# schematic.net
KiCad netlist of a schematic drawn in EAGLE
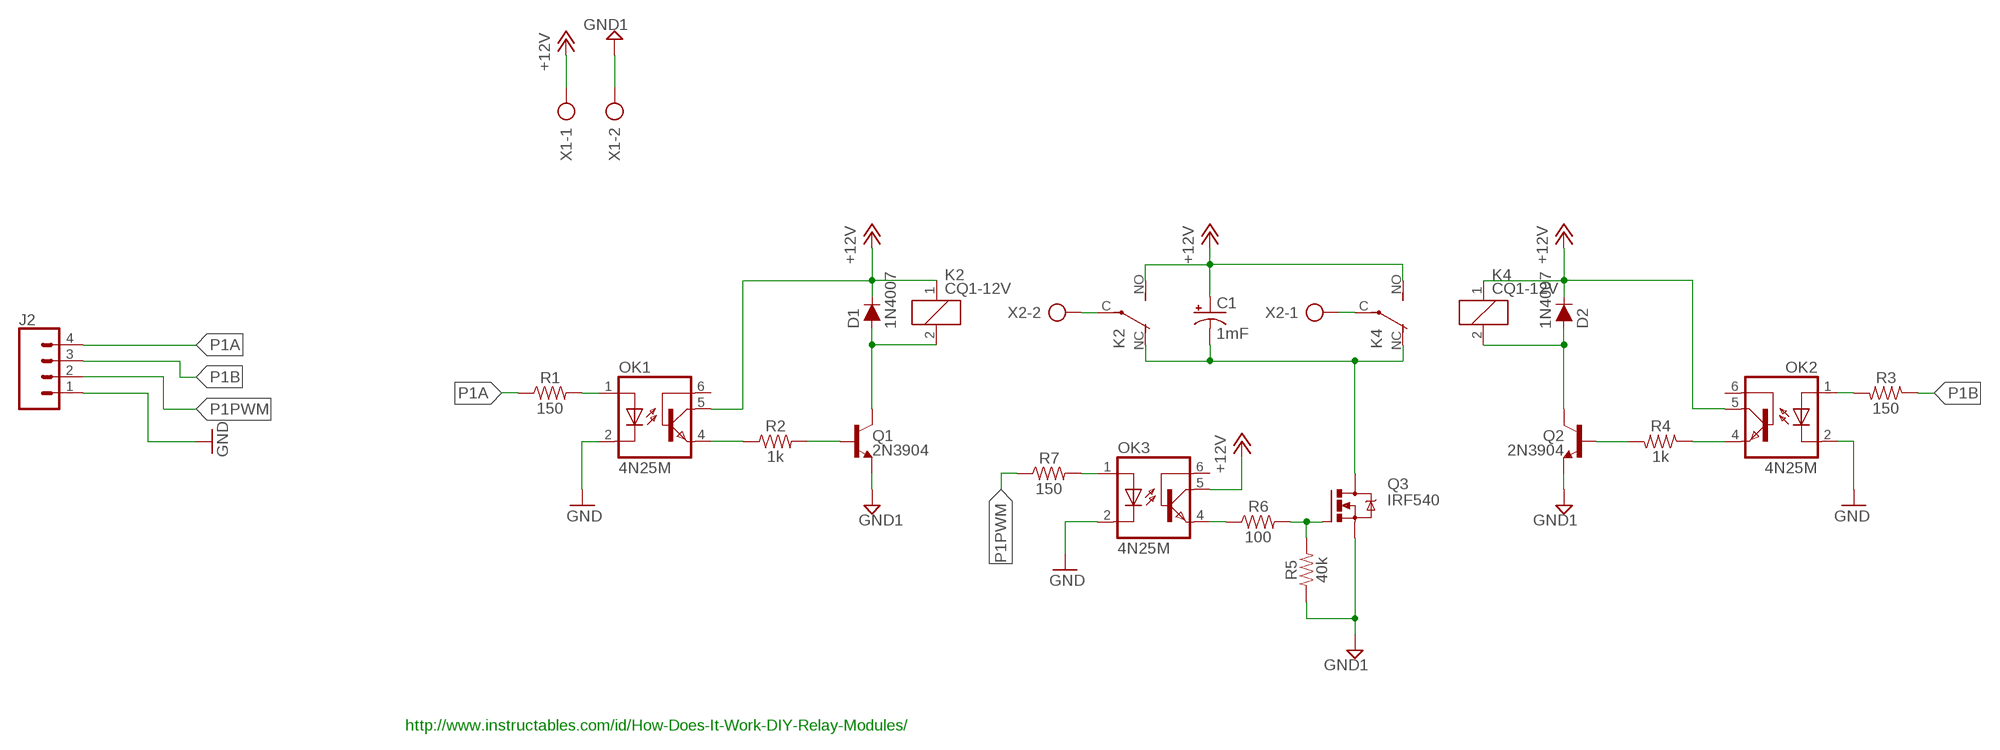
[diagram p0: schematic, sheet 1]

(export (version "E")
  (design (tool "Eeschema 10.0.6"))
  (components
    (comp (ref "C1")
      (value "1mF")
      (footprint "eagle-import:CPOL-RADIAL-5MM-10MM")
      (libsource (lib "eagle-import") (part "1000UF-RADIAL-5MM-25V-20%"))
    )
    (comp (ref "D1")
      (value "1N4007")
      (footprint "eagle-import:DIODE-1N4001")
      (libsource (lib "eagle-import") (part "DIODE-PTH"))
    )
    (comp (ref "D2")
      (value "1N4007")
      (footprint "eagle-import:DIODE-1N4001")
      (libsource (lib "eagle-import") (part "DIODE-PTH"))
    )
    (comp (ref "J2")
      (value "CONN_04LOCK_LONGPADS")
      (footprint "eagle-import:1X04_LOCK_LONGPADS")
      (libsource (lib "eagle-import") (part "CONN_04LOCK_LONGPADS"))
    )
    (comp (ref "K2")
      (value "CQ1-12V")
      (footprint "eagle-import:CQ1")
      (libsource (lib "eagle-import") (part "CQ1-12V"))
    )
    (comp (ref "K4")
      (value "CQ1-12V")
      (footprint "eagle-import:CQ1")
      (libsource (lib "eagle-import") (part "CQ1-12V"))
    )
    (comp (ref "OK1")
      (value "4N25M")
      (footprint "eagle-import:DIL06")
      (fields (field (name "MPN") "4N25-M"))
      (libsource (lib "eagle-import") (part "4N?M25"))
    )
    (comp (ref "OK2")
      (value "4N25M")
      (footprint "eagle-import:DIL06")
      (fields (field (name "MPN") "4N25-M"))
      (libsource (lib "eagle-import") (part "4N?M25"))
    )
    (comp (ref "OK3")
      (value "4N25M")
      (footprint "eagle-import:DIL06")
      (fields (field (name "MPN") "4N25-M"))
      (libsource (lib "eagle-import") (part "4N?M25"))
    )
    (comp (ref "Q1")
      (value "2N3904")
      (footprint "eagle-import:TO-92")
      (libsource (lib "eagle-import") (part "TRANS_NPN-2N3904"))
    )
    (comp (ref "Q2")
      (value "2N3904")
      (footprint "eagle-import:TO-92")
      (libsource (lib "eagle-import") (part "TRANS_NPN-2N3904"))
    )
    (comp (ref "Q3")
      (value "IRF540")
      (footprint "eagle-import:TO220BV")
      (libsource (lib "eagle-import") (part "IRF540"))
    )
    (comp (ref "R1")
      (value "150")
      (footprint "eagle-import:AXIAL-0.3")
      (libsource (lib "eagle-import") (part "10KOHM-HORIZ-1/4W-1%"))
    )
    (comp (ref "R2")
      (value "1k")
      (footprint "eagle-import:AXIAL-0.3")
      (libsource (lib "eagle-import") (part "10KOHM-HORIZ-1/4W-1%"))
    )
    (comp (ref "R3")
      (value "150")
      (footprint "eagle-import:AXIAL-0.3")
      (libsource (lib "eagle-import") (part "10KOHM-HORIZ-1/4W-1%"))
    )
    (comp (ref "R4")
      (value "1k")
      (footprint "eagle-import:AXIAL-0.3")
      (libsource (lib "eagle-import") (part "10KOHM-HORIZ-1/4W-1%"))
    )
    (comp (ref "R5")
      (value "40k")
      (footprint "eagle-import:AXIAL-0.3")
      (libsource (lib "eagle-import") (part "10KOHM-HORIZ-1/4W-1%"))
    )
    (comp (ref "R6")
      (value "100")
      (footprint "eagle-import:AXIAL-0.3")
      (libsource (lib "eagle-import") (part "10KOHM-HORIZ-1/4W-1%"))
    )
    (comp (ref "R7")
      (value "150")
      (footprint "eagle-import:AXIAL-0.3")
      (libsource (lib "eagle-import") (part "10KOHM-HORIZ-1/4W-1%"))
    )
    (comp (ref "X1")
      (value "AK300/2")
      (footprint "eagle-import:AK300_2")
      (libsource (lib "eagle-import") (part "AK300/2"))
    )
    (comp (ref "X2")
      (value "AK300/2")
      (footprint "eagle-import:AK300_2")
      (libsource (lib "eagle-import") (part "AK300/2"))
    )
  )
  (nets
    (net (code "1") (name "+12V") (class "Default")
      (node (ref "C1") (pin "+") (pinfunction "+_+") (pintype "passive"))
      (node (ref "D1") (pin "C") (pinfunction "C_C") (pintype "passive"))
      (node (ref "D2") (pin "C") (pinfunction "C_C") (pintype "passive"))
      (node (ref "K2") (pin "1") (pinfunction "1_1") (pintype "passive"))
      (node (ref "K2") (pin "NO") (pinfunction "S_NO") (pintype "passive"))
      (node (ref "K4") (pin "1") (pinfunction "1_1") (pintype "passive"))
      (node (ref "K4") (pin "NO") (pinfunction "S_NO") (pintype "passive"))
      (node (ref "OK1") (pin "5") (pinfunction "COL_5") (pintype "passive"))
      (node (ref "OK2") (pin "5") (pinfunction "COL_5") (pintype "passive"))
      (node (ref "OK3") (pin "5") (pinfunction "COL_5") (pintype "passive"))
      (node (ref "X1") (pin "1") (pinfunction "KL_1") (pintype "passive"))
    )
    (net (code "2") (name "GND") (class "Default")
      (node (ref "J2") (pin "1") (pinfunction "1_1") (pintype "passive"))
      (node (ref "OK1") (pin "2") (pinfunction "C_2") (pintype "passive"))
      (node (ref "OK2") (pin "2") (pinfunction "C_2") (pintype "passive"))
      (node (ref "OK3") (pin "2") (pinfunction "C_2") (pintype "passive"))
    )
    (net (code "3") (name "GND1") (class "Default")
      (node (ref "Q1") (pin "1") (pinfunction "E_1") (pintype "passive"))
      (node (ref "Q2") (pin "1") (pinfunction "E_1") (pintype "passive"))
      (node (ref "Q3") (pin "S") (pinfunction "S_S") (pintype "passive"))
      (node (ref "R5") (pin "P$1") (pinfunction "1_P$1") (pintype "passive"))
      (node (ref "X1") (pin "2") (pinfunction "KL_2") (pintype "passive"))
    )
    (net (code "4") (name "Net-(K2B-O)") (class "Default")
      (node (ref "C1") (pin "-") (pinfunction "-_-") (pintype "passive"))
      (node (ref "K2") (pin "NC") (pinfunction "O_NC") (pintype "passive"))
      (node (ref "K4") (pin "NC") (pinfunction "O_NC") (pintype "passive"))
      (node (ref "Q3") (pin "D") (pinfunction "D_D") (pintype "passive"))
    )
    (net (code "5") (name "Net-(K2B-P)") (class "Default")
      (node (ref "K2") (pin "C") (pinfunction "P_C") (pintype "passive"))
      (node (ref "X2") (pin "2") (pinfunction "KL_2") (pintype "passive"))
    )
    (net (code "6") (name "Net-(K4B-P)") (class "Default")
      (node (ref "K4") (pin "C") (pinfunction "P_C") (pintype "passive"))
      (node (ref "X2") (pin "1") (pinfunction "KL_1") (pintype "passive"))
    )
    (net (code "7") (name "Net-(OK1-A)") (class "Default")
      (node (ref "OK1") (pin "1") (pinfunction "A_1") (pintype "passive"))
      (node (ref "R1") (pin "P$2") (pinfunction "2_P$2") (pintype "passive"))
    )
    (net (code "8") (name "Net-(OK1-EMI)") (class "Default")
      (node (ref "OK1") (pin "4") (pinfunction "EMI_4") (pintype "passive"))
      (node (ref "R2") (pin "P$1") (pinfunction "1_P$1") (pintype "passive"))
    )
    (net (code "9") (name "Net-(OK2-A)") (class "Default")
      (node (ref "OK2") (pin "1") (pinfunction "A_1") (pintype "passive"))
      (node (ref "R3") (pin "P$2") (pinfunction "2_P$2") (pintype "passive"))
    )
    (net (code "10") (name "Net-(OK2-EMI)") (class "Default")
      (node (ref "OK2") (pin "4") (pinfunction "EMI_4") (pintype "passive"))
      (node (ref "R4") (pin "P$1") (pinfunction "1_P$1") (pintype "passive"))
    )
    (net (code "11") (name "Net-(OK3-A)") (class "Default")
      (node (ref "OK3") (pin "1") (pinfunction "A_1") (pintype "passive"))
      (node (ref "R7") (pin "P$2") (pinfunction "2_P$2") (pintype "passive"))
    )
    (net (code "12") (name "Net-(OK3-EMI)") (class "Default")
      (node (ref "OK3") (pin "4") (pinfunction "EMI_4") (pintype "passive"))
      (node (ref "R6") (pin "P$1") (pinfunction "1_P$1") (pintype "passive"))
    )
    (net (code "13") (name "Net-(Q1-B)") (class "Default")
      (node (ref "Q1") (pin "2") (pinfunction "B_2") (pintype "passive"))
      (node (ref "R2") (pin "P$2") (pinfunction "2_P$2") (pintype "passive"))
    )
    (net (code "14") (name "Net-(Q1-C)") (class "Default")
      (node (ref "D1") (pin "A") (pinfunction "A_A") (pintype "passive"))
      (node (ref "K2") (pin "2") (pinfunction "2_2") (pintype "passive"))
      (node (ref "Q1") (pin "3") (pinfunction "C_3") (pintype "passive"))
    )
    (net (code "15") (name "Net-(Q2-B)") (class "Default")
      (node (ref "Q2") (pin "2") (pinfunction "B_2") (pintype "passive"))
      (node (ref "R4") (pin "P$2") (pinfunction "2_P$2") (pintype "passive"))
    )
    (net (code "16") (name "Net-(Q2-C)") (class "Default")
      (node (ref "D2") (pin "A") (pinfunction "A_A") (pintype "passive"))
      (node (ref "K4") (pin "2") (pinfunction "2_2") (pintype "passive"))
      (node (ref "Q2") (pin "3") (pinfunction "C_3") (pintype "passive"))
    )
    (net (code "17") (name "Net-(R5-2)") (class "Default")
      (node (ref "Q3") (pin "G") (pinfunction "G_G") (pintype "passive"))
      (node (ref "R5") (pin "P$2") (pinfunction "2_P$2") (pintype "passive"))
      (node (ref "R6") (pin "P$2") (pinfunction "2_P$2") (pintype "passive"))
    )
    (net (code "18") (name "P1A") (class "Default")
      (node (ref "J2") (pin "4") (pinfunction "4_4") (pintype "passive"))
      (node (ref "R1") (pin "P$1") (pinfunction "1_P$1") (pintype "passive"))
    )
    (net (code "19") (name "P1B") (class "Default")
      (node (ref "J2") (pin "3") (pinfunction "3_3") (pintype "passive"))
      (node (ref "R3") (pin "P$1") (pinfunction "1_P$1") (pintype "passive"))
    )
    (net (code "20") (name "P1PWM") (class "Default")
      (node (ref "J2") (pin "2") (pinfunction "2_2") (pintype "passive"))
      (node (ref "R7") (pin "P$1") (pinfunction "1_P$1") (pintype "passive"))
    )
    (net (code "21") (name "unconnected-(OK1-BAS-Pad6)") (class "Default")
      (node (ref "OK1") (pin "6") (pinfunction "BAS_6") (pintype "passive"))
    )
    (net (code "22") (name "unconnected-(OK2-BAS-Pad6)") (class "Default")
      (node (ref "OK2") (pin "6") (pinfunction "BAS_6") (pintype "passive"))
    )
    (net (code "23") (name "unconnected-(OK3-BAS-Pad6)") (class "Default")
      (node (ref "OK3") (pin "6") (pinfunction "BAS_6") (pintype "passive"))
    )
  )
)
